# Audio.net
KiCad netlist of a schematic drawn in Altium Designer
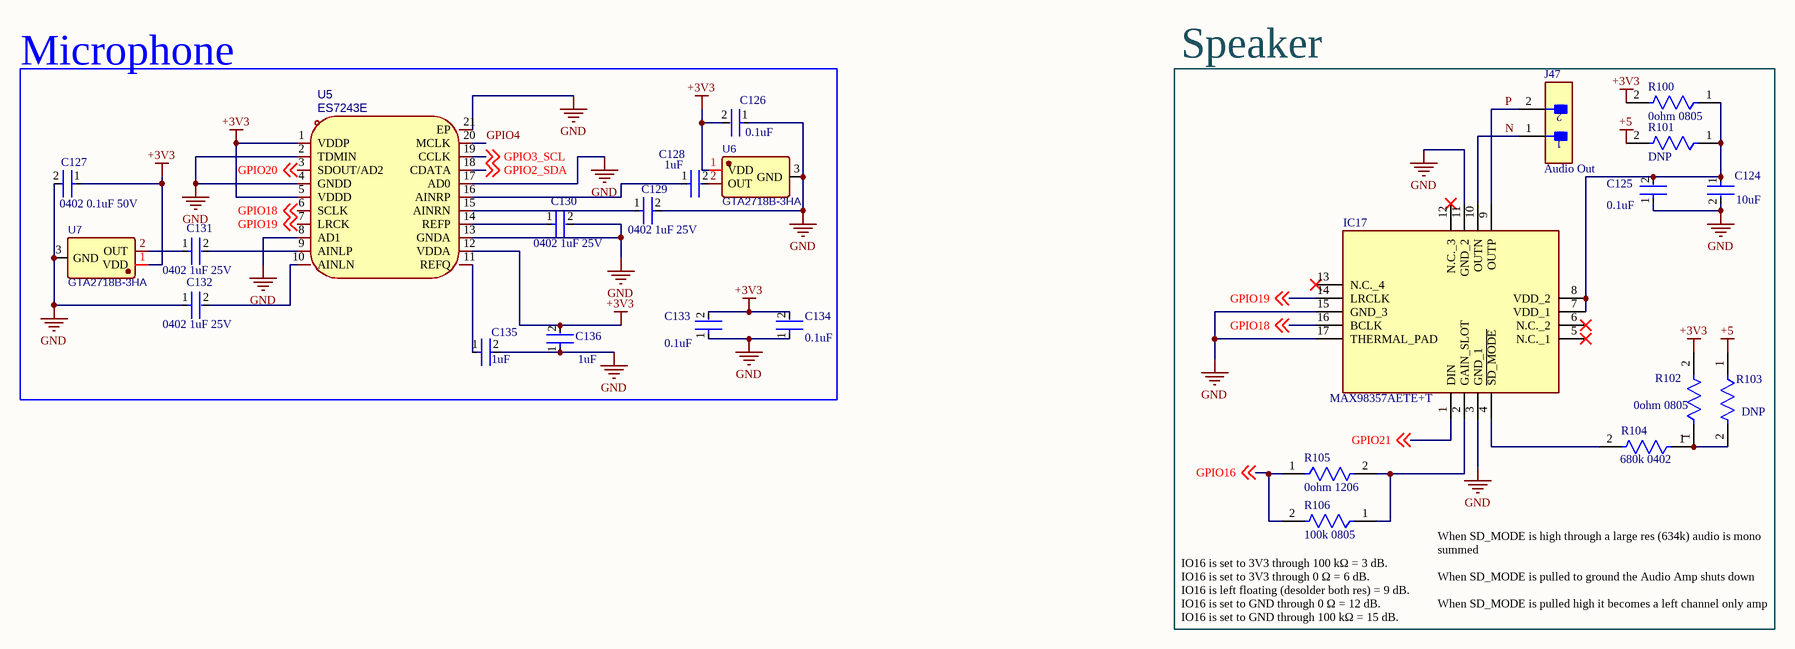
[diagram p0: Audio.SchDoc]

(export (version "E")
  (design (tool "Eeschema 10.0.6"))
  (components
    (comp (ref "C124")
      (value "10uF")
      (footprint "FP-CC0603-DC-MFG")
      (description "C96446")
      (fields (field (name "TOLERANCE") "10%"))
      (libsource (lib "Altium Content Vault") (part "b4654b650e69147ec39a6b967a45e02"))
    )
    (comp (ref "C125")
      (value "0.1uF")
      (footprint "FP-C0402-BB-MFG")
      (description "C307331")
      (fields
        (field (name "TOLERANCE") "0.2")
        (field (name "OCTOPART") "https://octopart.com/c0402c104m3pac7867-kemet-84304880")
      )
      (libsource (lib "Altium Content Vault") (part "b4654b650e69147ec39a6b967a45e02"))
    )
    (comp (ref "C126")
      (value "0.1uF")
      (footprint "FP-C0402-BB-MFG")
      (description "C307331")
      (fields
        (field (name "TOLERANCE") "0.2")
        (field (name "OCTOPART") "https://octopart.com/c0402c104m3pac7867-kemet-84304880")
      )
      (libsource (lib "Altium Content Vault") (part "b4654b650e69147ec39a6b967a45e02"))
    )
    (comp (ref "C127")
      (value "0402 0.1uF 50V")
      (footprint "FP-C0402-BB-MFG")
      (description "C307331")
      (fields
        (field (name "TOLERANCE") "0.2")
        (field (name "OCTOPART") "https://octopart.com/c0402c104m3pac7867-kemet-84304880")
      )
      (libsource (lib "Altium Content Vault") (part "b4654b650e69147ec39a6b967a45e02"))
    )
    (comp (ref "C128")
      (value "1uF")
      (footprint "FP-C0402-BB-MFG")
      (description "C52923")
      (fields
        (field (name "TOLERANCE") "0.2")
        (field (name "OCTOPART") "https://octopart.com/c0402c104m3pac7867-kemet-84304880")
      )
      (libsource (lib "Altium Content Vault") (part "b4654b650e69147ec39a6b967a45e02"))
    )
    (comp (ref "C129")
      (value "0402 1uF 25V")
      (footprint "FP-C0402-BB-MFG")
      (description "C52923")
      (fields
        (field (name "TOLERANCE") "0.2")
        (field (name "OCTOPART") "https://octopart.com/c0402c104m3pac7867-kemet-84304880")
      )
      (libsource (lib "Altium Content Vault") (part "b4654b650e69147ec39a6b967a45e02"))
    )
    (comp (ref "C130")
      (value "0402 1uF 25V")
      (footprint "FP-C0402-BB-MFG")
      (description "C52923")
      (fields
        (field (name "TOLERANCE") "0.2")
        (field (name "OCTOPART") "https://octopart.com/c0402c104m3pac7867-kemet-84304880")
      )
      (libsource (lib "Altium Content Vault") (part "b4654b650e69147ec39a6b967a45e02"))
    )
    (comp (ref "C131")
      (value "0402 1uF 25V")
      (footprint "FP-C0402-BB-MFG")
      (description "C52923")
      (fields
        (field (name "TOLERANCE") "0.2")
        (field (name "OCTOPART") "https://octopart.com/c0402c104m3pac7867-kemet-84304880")
      )
      (libsource (lib "Altium Content Vault") (part "b4654b650e69147ec39a6b967a45e02"))
    )
    (comp (ref "C132")
      (value "0402 1uF 25V")
      (footprint "FP-C0402-BB-MFG")
      (description "C52923")
      (fields
        (field (name "TOLERANCE") "0.2")
        (field (name "OCTOPART") "https://octopart.com/c0402c104m3pac7867-kemet-84304880")
      )
      (libsource (lib "Altium Content Vault") (part "b4654b650e69147ec39a6b967a45e02"))
    )
    (comp (ref "C133")
      (value "0.1uF")
      (footprint "FP-C0402-BB-MFG")
      (description "C307331")
      (fields
        (field (name "TOLERANCE") "0.2")
        (field (name "OCTOPART") "https://octopart.com/c0402c104m3pac7867-kemet-84304880")
      )
      (libsource (lib "Altium Content Vault") (part "b4654b650e69147ec39a6b967a45e02"))
    )
    (comp (ref "C134")
      (value "0.1uF")
      (footprint "FP-C0402-BB-MFG")
      (description "C307331")
      (fields
        (field (name "TOLERANCE") "0.2")
        (field (name "OCTOPART") "https://octopart.com/c0402c104m3pac7867-kemet-84304880")
      )
      (libsource (lib "Altium Content Vault") (part "b4654b650e69147ec39a6b967a45e02"))
    )
    (comp (ref "C135")
      (value "1uF")
      (footprint "FP-C0402-BB-MFG")
      (description "C52923")
      (fields
        (field (name "TOLERANCE") "0.2")
        (field (name "OCTOPART") "https://octopart.com/c0402c104m3pac7867-kemet-84304880")
      )
      (libsource (lib "Altium Content Vault") (part "b4654b650e69147ec39a6b967a45e02"))
    )
    (comp (ref "C136")
      (value "1uF")
      (footprint "FP-C0402-BB-MFG")
      (description "C52923")
      (fields
        (field (name "TOLERANCE") "0.2")
        (field (name "OCTOPART") "https://octopart.com/c0402c104m3pac7867-kemet-84304880")
      )
      (libsource (lib "Altium Content Vault") (part "b4654b650e69147ec39a6b967a45e02"))
    )
    (comp (ref "IC17")
      (value "MAX98357AETE+T")
      (footprint "SamacSys:QFN50P300X300X80-17N")
      (description "C910544")
      (fields (field (name "MOUSER PART NUMBER") "700-MAX98357AETE+T"))
      (libsource (lib "*") (part "MAX98357AETE+T"))
    )
    (comp (ref "J47")
      (value "Audio Out")
      (footprint "FP-TSW-102-07-F-S-MFG")
      (description "CONN HEADER VERT 2POS 2.54MM")
      (libsource (lib "Altium Content Vault") (part "3bc925449376181038e59eaffc5286c"))
    )
    (comp (ref "R100")
      (value "0ohm 0805")
      (footprint "FP-RN73R2A-IPC_C")
      (description "C17477")
      (libsource (lib "Altium Content Vault") (part "1029c3af85768c4190bb7ad29bc67b5"))
    )
    (comp (ref "R101")
      (value "DNP")
      (footprint "FP-RN73R2A-IPC_C")
      (description "DNP 0805")
      (libsource (lib "Altium Content Vault") (part "1029c3af85768c4190bb7ad29bc67b5"))
    )
    (comp (ref "R102")
      (value "0ohm 0805")
      (footprint "FP-RN73R2A-IPC_C")
      (description "C17477")
      (libsource (lib "Altium Content Vault") (part "1029c3af85768c4190bb7ad29bc67b5"))
    )
    (comp (ref "R103")
      (value "DNP")
      (footprint "FP-RN73R2A-IPC_C")
      (description "DNP 0805")
      (libsource (lib "Altium Content Vault") (part "1029c3af85768c4190bb7ad29bc67b5"))
    )
    (comp (ref "R104")
      (value "680k 0402")
      (footprint "FP-AF0402-IPC_B")
      (description "C54920820")
      (fields (field (name "TOLERANCE") "5%"))
      (libsource (lib "Altium Content Vault") (part "1029c3af85768c4190bb7ad29bc67b5"))
    )
    (comp (ref "R105")
      (value "0ohm 1206")
      (footprint "FP-HCJ1206-MFG")
      (description "C17888")
      (libsource (lib "Altium Content Vault") (part "1029c3af85768c4190bb7ad29bc67b5"))
    )
    (comp (ref "R106")
      (value "100k 0805")
      (footprint "FP-RN73R2A-IPC_C")
      (description "C149504")
      (libsource (lib "Altium Content Vault") (part "1029c3af85768c4190bb7ad29bc67b5"))
    )
    (comp (ref "U5")
      (value "ES7243E")
      (footprint "QFN-20_L3.0-W3.0-P0.40-BL-EP1.7")
      (description "C2929446")
      (fields (field (name "MANUFACTURER") "Everest-semi(顺芯)"))
      (libsource (lib "Schlib1") (part "ES7243E"))
    )
    (comp (ref "U6")
      (value "GTA2718B-3HA")
      (footprint "MIC-SMD_3P-L2.8-W1.9_AP1688")
      (description "C50275773")
      (fields (field (name "MANUFACTURER") "Gettop(共达)") (field (name "CONTRIBUTOR") "lcsc"))
      (libsource (lib "Schlib1") (part "GTA2718B-3HA"))
    )
    (comp (ref "U7")
      (value "GTA2718B-3HA")
      (footprint "MIC-SMD_3P-L2.8-W1.9_AP1688")
      (description "C50275773")
      (fields (field (name "MANUFACTURER") "Gettop(共达)") (field (name "CONTRIBUTOR") "lcsc"))
      (libsource (lib "Schlib1") (part "GTA2718B-3HA"))
    )
  )
  (nets
    (net (code "1") (name "+3V3") (class "Default")
      (node (ref "C126") (pin "2") (pinfunction "2_2") (pintype "passive"))
      (node (ref "C127") (pin "1") (pinfunction "1_1") (pintype "passive"))
      (node (ref "C133") (pin "2") (pinfunction "2_2") (pintype "passive"))
      (node (ref "C134") (pin "2") (pinfunction "2_2") (pintype "passive"))
      (node (ref "C136") (pin "2") (pinfunction "2_2") (pintype "passive"))
      (node (ref "R100") (pin "2") (pinfunction "2_2") (pintype "passive"))
      (node (ref "R102") (pin "2") (pinfunction "2_2") (pintype "passive"))
      (node (ref "U5") (pin "1") (pinfunction "VDDP_1") (pintype "passive"))
      (node (ref "U5") (pin "12") (pinfunction "VDDA_12") (pintype "passive"))
      (node (ref "U5") (pin "5") (pinfunction "VDDD_5") (pintype "passive"))
      (node (ref "U6") (pin "1") (pinfunction "VDD_1") (pintype "passive"))
      (node (ref "U7") (pin "1") (pinfunction "VDD_1") (pintype "passive"))
    )
    (net (code "2") (name "+5") (class "Default")
      (node (ref "R101") (pin "2") (pinfunction "2_2") (pintype "passive"))
      (node (ref "R103") (pin "1") (pinfunction "1_1") (pintype "passive"))
    )
    (net (code "3") (name "/GPIO4") (class "Default")
      (node (ref "U5") (pin "20") (pinfunction "MCLK_20") (pintype "passive"))
    )
    (net (code "4") (name "/N") (class "Default")
      (node (ref "IC17") (pin "10") (pinfunction "OUTN_10") (pintype "passive"))
      (node (ref "J47") (pin "1") (pinfunction "1_1") (pintype "passive"))
    )
    (net (code "5") (name "/P") (class "Default")
      (node (ref "IC17") (pin "9") (pinfunction "OUTP_9") (pintype "passive"))
      (node (ref "J47") (pin "2") (pinfunction "2_2") (pintype "passive"))
    )
    (net (code "6") (name "GND") (class "Default")
      (node (ref "C124") (pin "2") (pinfunction "2_2") (pintype "passive"))
      (node (ref "C125") (pin "1") (pinfunction "1_1") (pintype "passive"))
      (node (ref "C126") (pin "1") (pinfunction "1_1") (pintype "passive"))
      (node (ref "C127") (pin "2") (pinfunction "2_2") (pintype "passive"))
      (node (ref "C129") (pin "2") (pinfunction "2_2") (pintype "passive"))
      (node (ref "C130") (pin "2") (pinfunction "2_2") (pintype "passive"))
      (node (ref "C132") (pin "1") (pinfunction "1_1") (pintype "passive"))
      (node (ref "C133") (pin "1") (pinfunction "1_1") (pintype "passive"))
      (node (ref "C134") (pin "1") (pinfunction "1_1") (pintype "passive"))
      (node (ref "C135") (pin "2") (pinfunction "2_2") (pintype "passive"))
      (node (ref "C136") (pin "1") (pinfunction "1_1") (pintype "passive"))
      (node (ref "IC17") (pin "11") (pinfunction "GND_2_11") (pintype "passive"))
      (node (ref "IC17") (pin "15") (pinfunction "GND_3_15") (pintype "passive"))
      (node (ref "IC17") (pin "17") (pinfunction "THERMAL_PAD_17") (pintype "passive"))
      (node (ref "IC17") (pin "3") (pinfunction "GND_1_3") (pintype "passive"))
      (node (ref "U5") (pin "13") (pinfunction "GNDA_13") (pintype "passive"))
      (node (ref "U5") (pin "17") (pinfunction "AD0_17") (pintype "passive"))
      (node (ref "U5") (pin "2") (pinfunction "TDMIN_2") (pintype "passive"))
      (node (ref "U5") (pin "21") (pinfunction "EP_21") (pintype "passive"))
      (node (ref "U5") (pin "4") (pinfunction "GNDD_4") (pintype "passive"))
      (node (ref "U5") (pin "8") (pinfunction "AD1_8") (pintype "passive"))
      (node (ref "U6") (pin "3") (pinfunction "GND_3") (pintype "passive"))
      (node (ref "U7") (pin "3") (pinfunction "GND_3") (pintype "passive"))
    )
    (net (code "7") (name "GPIO2_SDA") (class "Default")
      (node (ref "U5") (pin "18") (pinfunction "CDATA_18") (pintype "passive"))
    )
    (net (code "8") (name "GPIO3_SCL") (class "Default")
      (node (ref "U5") (pin "19") (pinfunction "CCLK_19") (pintype "passive"))
    )
    (net (code "9") (name "GPIO16") (class "Default")
      (node (ref "R105") (pin "1") (pinfunction "1_1") (pintype "passive"))
      (node (ref "R106") (pin "2") (pinfunction "2_2") (pintype "passive"))
    )
    (net (code "10") (name "GPIO18") (class "Default")
      (node (ref "IC17") (pin "16") (pinfunction "BCLK_16") (pintype "passive"))
      (node (ref "U5") (pin "6") (pinfunction "SCLK_6") (pintype "passive"))
    )
    (net (code "11") (name "GPIO19") (class "Default")
      (node (ref "IC17") (pin "14") (pinfunction "LRCLK_14") (pintype "passive"))
      (node (ref "U5") (pin "7") (pinfunction "LRCK_7") (pintype "passive"))
    )
    (net (code "12") (name "GPIO20") (class "Default")
      (node (ref "U5") (pin "3") (pinfunction "SDOUT/AD2_3") (pintype "passive"))
    )
    (net (code "13") (name "GPIO21") (class "Default")
      (node (ref "IC17") (pin "1") (pinfunction "DIN_1") (pintype "passive"))
    )
    (net (code "14") (name "Net-(IC17-GAIN_SLOT)") (class "Default")
      (node (ref "IC17") (pin "2") (pinfunction "GAIN_SLOT_2") (pintype "passive"))
      (node (ref "R105") (pin "2") (pinfunction "2_2") (pintype "passive"))
      (node (ref "R106") (pin "1") (pinfunction "1_1") (pintype "passive"))
    )
    (net (code "15") (name "Net-(IC17-VDD_1)") (class "Default")
      (node (ref "C124") (pin "1") (pinfunction "1_1") (pintype "passive"))
      (node (ref "C125") (pin "2") (pinfunction "2_2") (pintype "passive"))
      (node (ref "IC17") (pin "7") (pinfunction "VDD_1_7") (pintype "passive"))
      (node (ref "IC17") (pin "8") (pinfunction "VDD_2_8") (pintype "passive"))
      (node (ref "R100") (pin "1") (pinfunction "1_1") (pintype "passive"))
      (node (ref "R101") (pin "1") (pinfunction "1_1") (pintype "passive"))
    )
    (net (code "16") (name "Net-(IC17-~{SD_MODE})") (class "Default")
      (node (ref "IC17") (pin "4") (pinfunction "~{SD_MODE}_4") (pintype "passive"))
      (node (ref "R104") (pin "2") (pinfunction "2_2") (pintype "passive"))
    )
    (net (code "17") (name "Net-(R102-Pad1)") (class "Default")
      (node (ref "R102") (pin "1") (pinfunction "1_1") (pintype "passive"))
      (node (ref "R103") (pin "2") (pinfunction "2_2") (pintype "passive"))
      (node (ref "R104") (pin "1") (pinfunction "1_1") (pintype "passive"))
    )
    (net (code "18") (name "Net-(U5-AINLN)") (class "Default")
      (node (ref "C132") (pin "2") (pinfunction "2_2") (pintype "passive"))
      (node (ref "U5") (pin "10") (pinfunction "AINLN_10") (pintype "passive"))
    )
    (net (code "19") (name "Net-(U5-AINLP)") (class "Default")
      (node (ref "C131") (pin "2") (pinfunction "2_2") (pintype "passive"))
      (node (ref "U5") (pin "9") (pinfunction "AINLP_9") (pintype "passive"))
    )
    (net (code "20") (name "Net-(U5-AINRN)") (class "Default")
      (node (ref "C129") (pin "1") (pinfunction "1_1") (pintype "passive"))
      (node (ref "U5") (pin "15") (pinfunction "AINRN_15") (pintype "passive"))
    )
    (net (code "21") (name "Net-(U5-AINRP)") (class "Default")
      (node (ref "C128") (pin "1") (pinfunction "1_1") (pintype "passive"))
      (node (ref "U5") (pin "16") (pinfunction "AINRP_16") (pintype "passive"))
    )
    (net (code "22") (name "Net-(U5-REFP)") (class "Default")
      (node (ref "C130") (pin "1") (pinfunction "1_1") (pintype "passive"))
      (node (ref "U5") (pin "14") (pinfunction "REFP_14") (pintype "passive"))
    )
    (net (code "23") (name "Net-(U5-REFQ)") (class "Default")
      (node (ref "C135") (pin "1") (pinfunction "1_1") (pintype "passive"))
      (node (ref "U5") (pin "11") (pinfunction "REFQ_11") (pintype "passive"))
    )
    (net (code "24") (name "Net-(U6-OUT)") (class "Default")
      (node (ref "C128") (pin "2") (pinfunction "2_2") (pintype "passive"))
      (node (ref "U6") (pin "2") (pinfunction "OUT_2") (pintype "passive"))
    )
    (net (code "25") (name "Net-(U7-OUT)") (class "Default")
      (node (ref "C131") (pin "1") (pinfunction "1_1") (pintype "passive"))
      (node (ref "U7") (pin "2") (pinfunction "OUT_2") (pintype "passive"))
    )
    (net (code "26") (name "unconnected-(IC17-N.C._1-Pad5)") (class "Default")
      (node (ref "IC17") (pin "5") (pinfunction "N.C._1_5") (pintype "passive+no_connect"))
    )
    (net (code "27") (name "unconnected-(IC17-N.C._2-Pad6)") (class "Default")
      (node (ref "IC17") (pin "6") (pinfunction "N.C._2_6") (pintype "passive+no_connect"))
    )
    (net (code "28") (name "unconnected-(IC17-N.C._3-Pad12)") (class "Default")
      (node (ref "IC17") (pin "12") (pinfunction "N.C._3_12") (pintype "passive+no_connect"))
    )
    (net (code "29") (name "unconnected-(IC17-N.C._4-Pad13)") (class "Default")
      (node (ref "IC17") (pin "13") (pinfunction "N.C._4_13") (pintype "passive+no_connect"))
    )
  )
)
